# Leds_Switches.net
KiCad netlist of a schematic drawn in Altium Designer
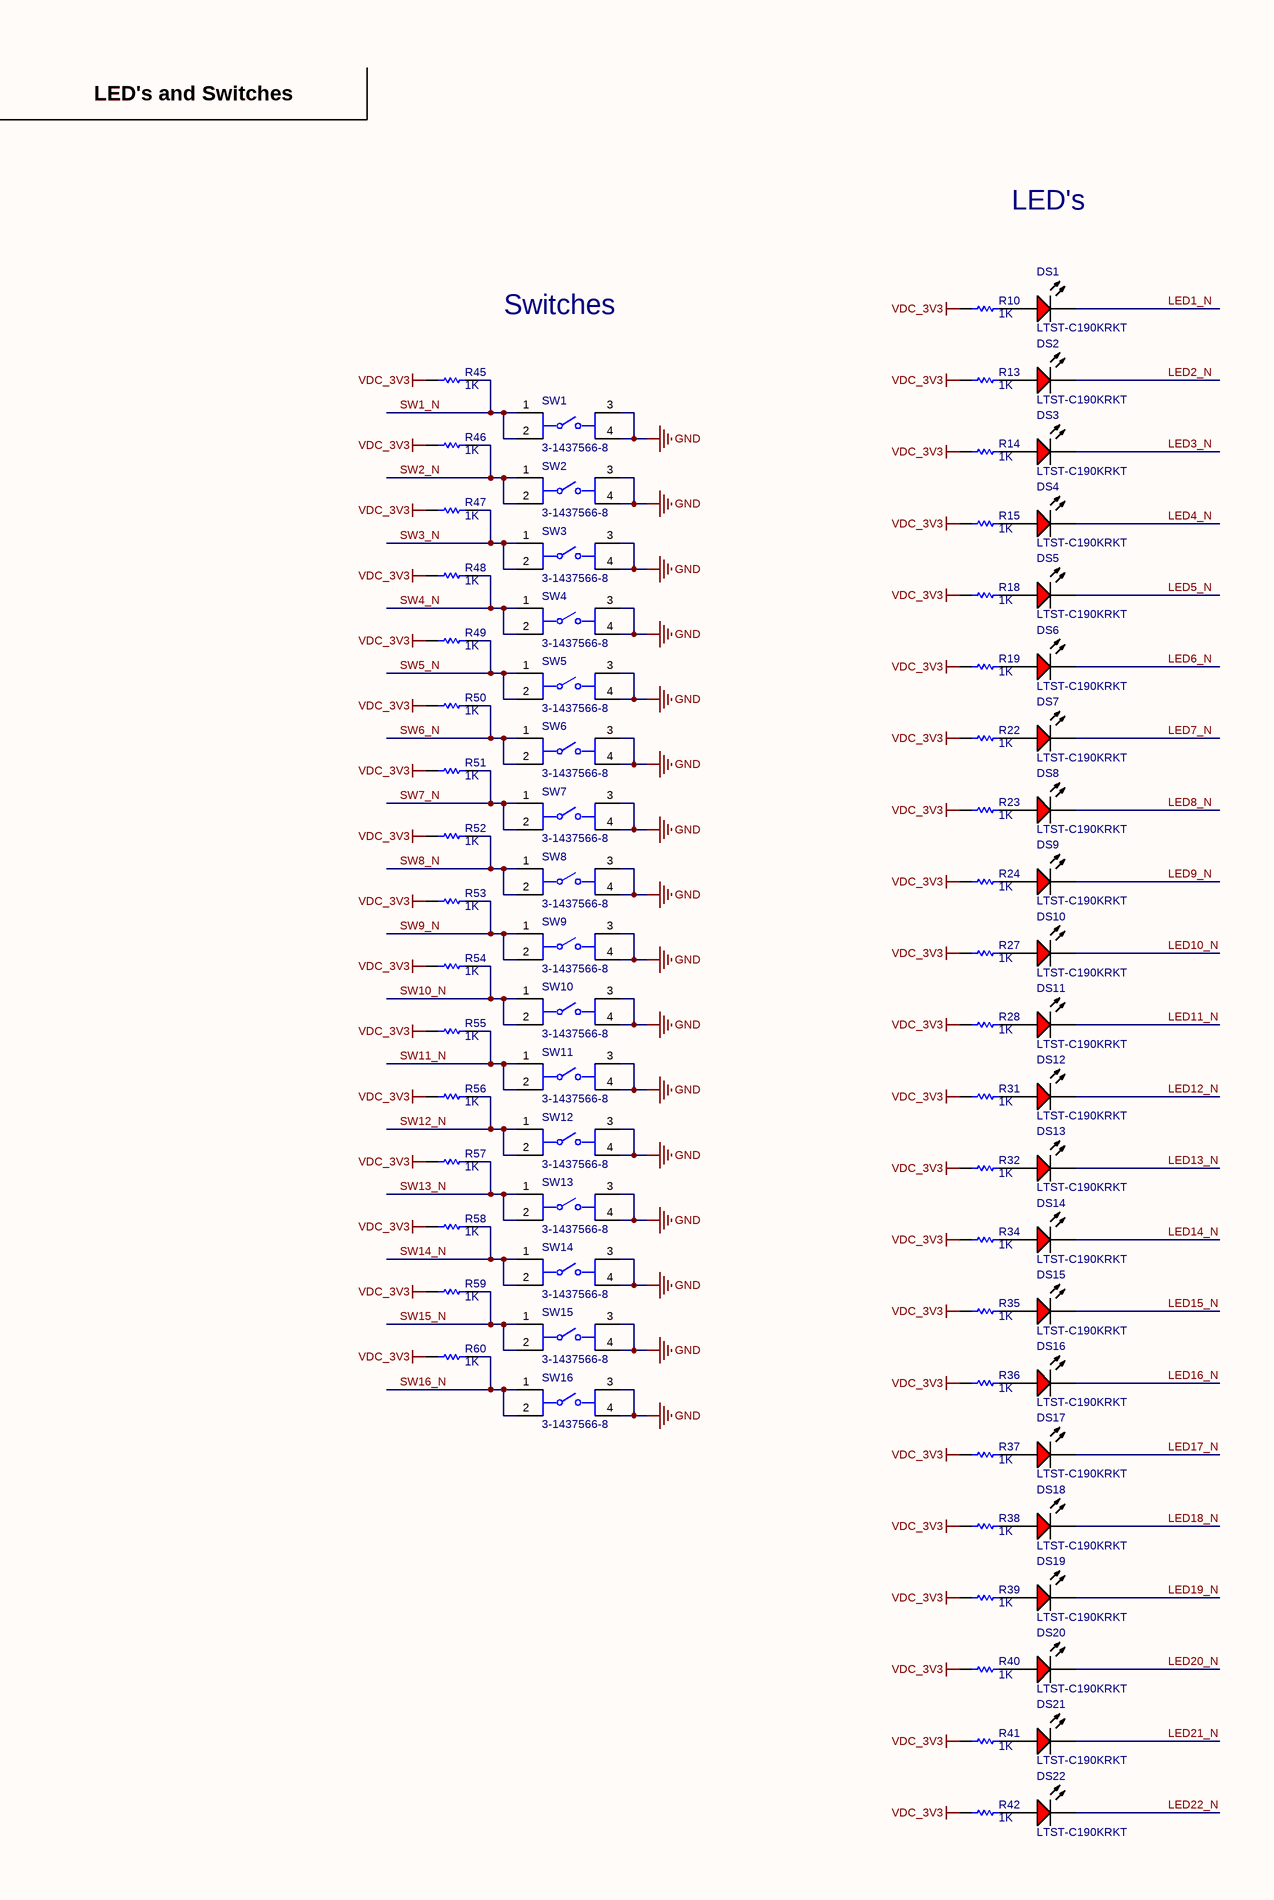
[diagram p0: Leds Switches.SchDoc, left]
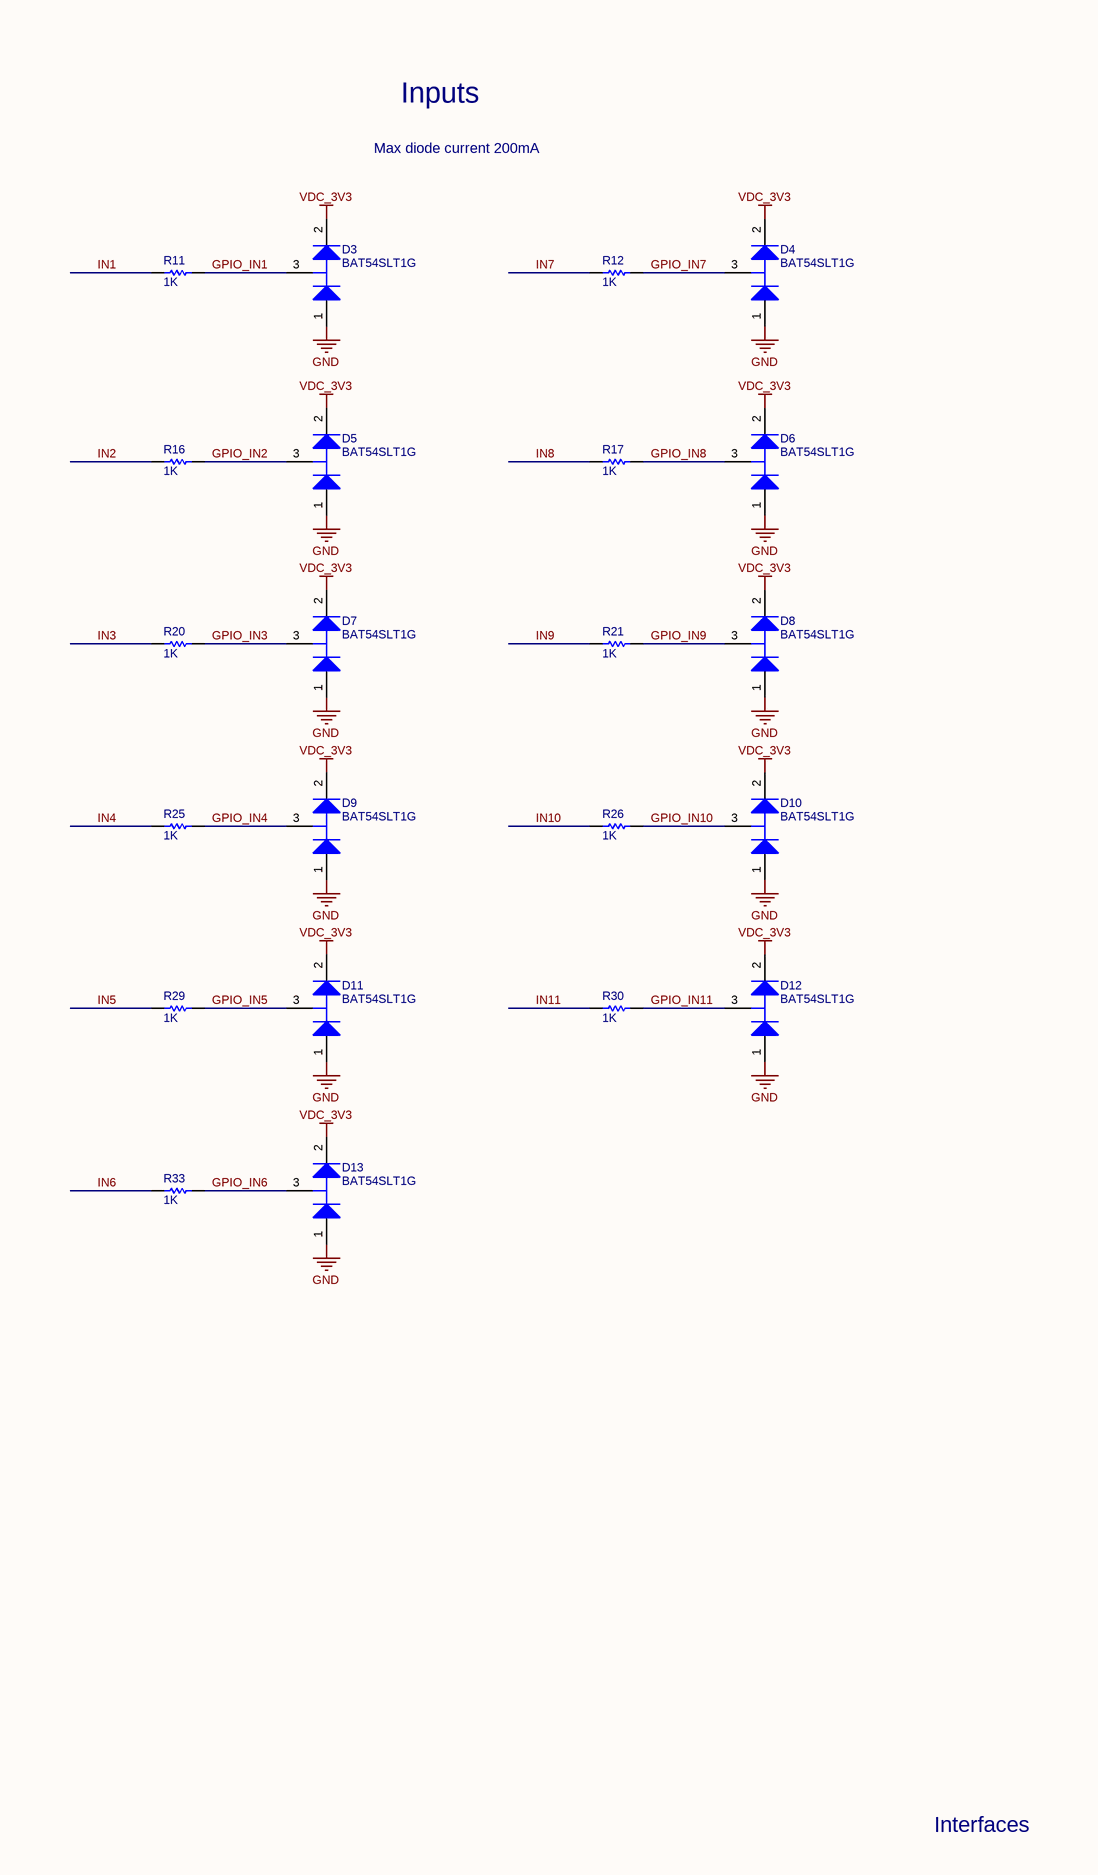
[diagram p1: Leds Switches.SchDoc, right]

(export (version "E")
  (design (tool "Eeschema 10.0.6"))
  (components
    (comp (ref "D3")
      (value "BAT54SLT1G")
      (footprint "ONSC-SOT-23-3-318-08_V")
      (description "Dual Series Schottky Barrier Diodes, 3-Pin SOT-23, Pb-Free, Tape and Reel")
      (fields (field (name "MANUFACTURER") "On Semiconductor"))
      (libsource (lib "Altium Content Vault") (part "ONSC-D-A1K2C3-3"))
    )
    (comp (ref "D4")
      (value "BAT54SLT1G")
      (footprint "ONSC-SOT-23-3-318-08_V")
      (description "Dual Series Schottky Barrier Diodes, 3-Pin SOT-23, Pb-Free, Tape and Reel")
      (fields (field (name "MANUFACTURER") "On Semiconductor"))
      (libsource (lib "Altium Content Vault") (part "ONSC-D-A1K2C3-3"))
    )
    (comp (ref "D5")
      (value "BAT54SLT1G")
      (footprint "ONSC-SOT-23-3-318-08_V")
      (description "Dual Series Schottky Barrier Diodes, 3-Pin SOT-23, Pb-Free, Tape and Reel")
      (fields (field (name "MANUFACTURER") "On Semiconductor"))
      (libsource (lib "Altium Content Vault") (part "ONSC-D-A1K2C3-3"))
    )
    (comp (ref "D6")
      (value "BAT54SLT1G")
      (footprint "ONSC-SOT-23-3-318-08_V")
      (description "Dual Series Schottky Barrier Diodes, 3-Pin SOT-23, Pb-Free, Tape and Reel")
      (fields (field (name "MANUFACTURER") "On Semiconductor"))
      (libsource (lib "Altium Content Vault") (part "ONSC-D-A1K2C3-3"))
    )
    (comp (ref "D7")
      (value "BAT54SLT1G")
      (footprint "ONSC-SOT-23-3-318-08_V")
      (description "Dual Series Schottky Barrier Diodes, 3-Pin SOT-23, Pb-Free, Tape and Reel")
      (fields (field (name "MANUFACTURER") "On Semiconductor"))
      (libsource (lib "Altium Content Vault") (part "ONSC-D-A1K2C3-3"))
    )
    (comp (ref "D8")
      (value "BAT54SLT1G")
      (footprint "ONSC-SOT-23-3-318-08_V")
      (description "Dual Series Schottky Barrier Diodes, 3-Pin SOT-23, Pb-Free, Tape and Reel")
      (fields (field (name "MANUFACTURER") "On Semiconductor"))
      (libsource (lib "Altium Content Vault") (part "ONSC-D-A1K2C3-3"))
    )
    (comp (ref "D9")
      (value "BAT54SLT1G")
      (footprint "ONSC-SOT-23-3-318-08_V")
      (description "Dual Series Schottky Barrier Diodes, 3-Pin SOT-23, Pb-Free, Tape and Reel")
      (fields (field (name "MANUFACTURER") "On Semiconductor"))
      (libsource (lib "Altium Content Vault") (part "ONSC-D-A1K2C3-3"))
    )
    (comp (ref "D10")
      (value "BAT54SLT1G")
      (footprint "ONSC-SOT-23-3-318-08_V")
      (description "Dual Series Schottky Barrier Diodes, 3-Pin SOT-23, Pb-Free, Tape and Reel")
      (fields (field (name "MANUFACTURER") "On Semiconductor"))
      (libsource (lib "Altium Content Vault") (part "ONSC-D-A1K2C3-3"))
    )
    (comp (ref "D11")
      (value "BAT54SLT1G")
      (footprint "ONSC-SOT-23-3-318-08_V")
      (description "Dual Series Schottky Barrier Diodes, 3-Pin SOT-23, Pb-Free, Tape and Reel")
      (fields (field (name "MANUFACTURER") "On Semiconductor"))
      (libsource (lib "Altium Content Vault") (part "ONSC-D-A1K2C3-3"))
    )
    (comp (ref "D12")
      (value "BAT54SLT1G")
      (footprint "ONSC-SOT-23-3-318-08_V")
      (description "Dual Series Schottky Barrier Diodes, 3-Pin SOT-23, Pb-Free, Tape and Reel")
      (fields (field (name "MANUFACTURER") "On Semiconductor"))
      (libsource (lib "Altium Content Vault") (part "ONSC-D-A1K2C3-3"))
    )
    (comp (ref "D13")
      (value "BAT54SLT1G")
      (footprint "ONSC-SOT-23-3-318-08_V")
      (description "Dual Series Schottky Barrier Diodes, 3-Pin SOT-23, Pb-Free, Tape and Reel")
      (fields (field (name "MANUFACTURER") "On Semiconductor"))
      (libsource (lib "Altium Content Vault") (part "ONSC-D-A1K2C3-3"))
    )
    (comp (ref "DS1")
      (value "LTST-C190KRKT")
      (footprint "LTST-C191KRKT_V")
      (description "LED Uni-Color Red, 62.5 mW, 5 V, -30 to 85 degC, 2-Pin SMD, RoHS, Tape and Reel")
      (fields (field (name "TOLERANCE") "20%"))
      (libsource (lib "Altium Content Vault") (part "LED-RED-AK-2"))
    )
    (comp (ref "DS2")
      (value "LTST-C190KRKT")
      (footprint "LTST-C191KRKT_V")
      (description "LED Uni-Color Red, 62.5 mW, 5 V, -30 to 85 degC, 2-Pin SMD, RoHS, Tape and Reel")
      (fields (field (name "TOLERANCE") "20%"))
      (libsource (lib "Altium Content Vault") (part "LED-RED-AK-2"))
    )
    (comp (ref "DS3")
      (value "LTST-C190KRKT")
      (footprint "LTST-C191KRKT_V")
      (description "LED Uni-Color Red, 62.5 mW, 5 V, -30 to 85 degC, 2-Pin SMD, RoHS, Tape and Reel")
      (fields (field (name "TOLERANCE") "20%"))
      (libsource (lib "Altium Content Vault") (part "LED-RED-AK-2"))
    )
    (comp (ref "DS4")
      (value "LTST-C190KRKT")
      (footprint "LTST-C191KRKT_V")
      (description "LED Uni-Color Red, 62.5 mW, 5 V, -30 to 85 degC, 2-Pin SMD, RoHS, Tape and Reel")
      (fields (field (name "TOLERANCE") "20%"))
      (libsource (lib "Altium Content Vault") (part "LED-RED-AK-2"))
    )
    (comp (ref "DS5")
      (value "LTST-C190KRKT")
      (footprint "LTST-C191KRKT_V")
      (description "LED Uni-Color Red, 62.5 mW, 5 V, -30 to 85 degC, 2-Pin SMD, RoHS, Tape and Reel")
      (fields (field (name "TOLERANCE") "20%"))
      (libsource (lib "Altium Content Vault") (part "LED-RED-AK-2"))
    )
    (comp (ref "DS6")
      (value "LTST-C190KRKT")
      (footprint "LTST-C191KRKT_V")
      (description "LED Uni-Color Red, 62.5 mW, 5 V, -30 to 85 degC, 2-Pin SMD, RoHS, Tape and Reel")
      (fields (field (name "TOLERANCE") "20%"))
      (libsource (lib "Altium Content Vault") (part "LED-RED-AK-2"))
    )
    (comp (ref "DS7")
      (value "LTST-C190KRKT")
      (footprint "LTST-C191KRKT_V")
      (description "LED Uni-Color Red, 62.5 mW, 5 V, -30 to 85 degC, 2-Pin SMD, RoHS, Tape and Reel")
      (fields (field (name "TOLERANCE") "20%"))
      (libsource (lib "Altium Content Vault") (part "LED-RED-AK-2"))
    )
    (comp (ref "DS8")
      (value "LTST-C190KRKT")
      (footprint "LTST-C191KRKT_V")
      (description "LED Uni-Color Red, 62.5 mW, 5 V, -30 to 85 degC, 2-Pin SMD, RoHS, Tape and Reel")
      (fields (field (name "TOLERANCE") "20%"))
      (libsource (lib "Altium Content Vault") (part "LED-RED-AK-2"))
    )
    (comp (ref "DS9")
      (value "LTST-C190KRKT")
      (footprint "LTST-C191KRKT_V")
      (description "LED Uni-Color Red, 62.5 mW, 5 V, -30 to 85 degC, 2-Pin SMD, RoHS, Tape and Reel")
      (fields (field (name "TOLERANCE") "20%"))
      (libsource (lib "Altium Content Vault") (part "LED-RED-AK-2"))
    )
    (comp (ref "DS10")
      (value "LTST-C190KRKT")
      (footprint "LTST-C191KRKT_V")
      (description "LED Uni-Color Red, 62.5 mW, 5 V, -30 to 85 degC, 2-Pin SMD, RoHS, Tape and Reel")
      (fields (field (name "TOLERANCE") "20%"))
      (libsource (lib "Altium Content Vault") (part "LED-RED-AK-2"))
    )
    (comp (ref "DS11")
      (value "LTST-C190KRKT")
      (footprint "LTST-C191KRKT_V")
      (description "LED Uni-Color Red, 62.5 mW, 5 V, -30 to 85 degC, 2-Pin SMD, RoHS, Tape and Reel")
      (fields (field (name "TOLERANCE") "20%"))
      (libsource (lib "Altium Content Vault") (part "LED-RED-AK-2"))
    )
    (comp (ref "DS12")
      (value "LTST-C190KRKT")
      (footprint "LTST-C191KRKT_V")
      (description "LED Uni-Color Red, 62.5 mW, 5 V, -30 to 85 degC, 2-Pin SMD, RoHS, Tape and Reel")
      (fields (field (name "TOLERANCE") "20%"))
      (libsource (lib "Altium Content Vault") (part "LED-RED-AK-2"))
    )
    (comp (ref "DS13")
      (value "LTST-C190KRKT")
      (footprint "LTST-C191KRKT_V")
      (description "LED Uni-Color Red, 62.5 mW, 5 V, -30 to 85 degC, 2-Pin SMD, RoHS, Tape and Reel")
      (fields (field (name "TOLERANCE") "20%"))
      (libsource (lib "Altium Content Vault") (part "LED-RED-AK-2"))
    )
    (comp (ref "DS14")
      (value "LTST-C190KRKT")
      (footprint "LTST-C191KRKT_V")
      (description "LED Uni-Color Red, 62.5 mW, 5 V, -30 to 85 degC, 2-Pin SMD, RoHS, Tape and Reel")
      (fields (field (name "TOLERANCE") "20%"))
      (libsource (lib "Altium Content Vault") (part "LED-RED-AK-2"))
    )
    (comp (ref "DS15")
      (value "LTST-C190KRKT")
      (footprint "LTST-C191KRKT_V")
      (description "LED Uni-Color Red, 62.5 mW, 5 V, -30 to 85 degC, 2-Pin SMD, RoHS, Tape and Reel")
      (fields (field (name "TOLERANCE") "20%"))
      (libsource (lib "Altium Content Vault") (part "LED-RED-AK-2"))
    )
    (comp (ref "DS16")
      (value "LTST-C190KRKT")
      (footprint "LTST-C191KRKT_V")
      (description "LED Uni-Color Red, 62.5 mW, 5 V, -30 to 85 degC, 2-Pin SMD, RoHS, Tape and Reel")
      (fields (field (name "TOLERANCE") "20%"))
      (libsource (lib "Altium Content Vault") (part "LED-RED-AK-2"))
    )
    (comp (ref "DS17")
      (value "LTST-C190KRKT")
      (footprint "LTST-C191KRKT_V")
      (description "LED Uni-Color Red, 62.5 mW, 5 V, -30 to 85 degC, 2-Pin SMD, RoHS, Tape and Reel")
      (fields (field (name "TOLERANCE") "20%"))
      (libsource (lib "Altium Content Vault") (part "LED-RED-AK-2"))
    )
    (comp (ref "DS18")
      (value "LTST-C190KRKT")
      (footprint "LTST-C191KRKT_V")
      (description "LED Uni-Color Red, 62.5 mW, 5 V, -30 to 85 degC, 2-Pin SMD, RoHS, Tape and Reel")
      (fields (field (name "TOLERANCE") "20%"))
      (libsource (lib "Altium Content Vault") (part "LED-RED-AK-2"))
    )
    (comp (ref "DS19")
      (value "LTST-C190KRKT")
      (footprint "LTST-C191KRKT_V")
      (description "LED Uni-Color Red, 62.5 mW, 5 V, -30 to 85 degC, 2-Pin SMD, RoHS, Tape and Reel")
      (fields (field (name "TOLERANCE") "20%"))
      (libsource (lib "Altium Content Vault") (part "LED-RED-AK-2"))
    )
    (comp (ref "DS20")
      (value "LTST-C190KRKT")
      (footprint "LTST-C191KRKT_V")
      (description "LED Uni-Color Red, 62.5 mW, 5 V, -30 to 85 degC, 2-Pin SMD, RoHS, Tape and Reel")
      (fields (field (name "TOLERANCE") "20%"))
      (libsource (lib "Altium Content Vault") (part "LED-RED-AK-2"))
    )
    (comp (ref "DS21")
      (value "LTST-C190KRKT")
      (footprint "LTST-C191KRKT_V")
      (description "LED Uni-Color Red, 62.5 mW, 5 V, -30 to 85 degC, 2-Pin SMD, RoHS, Tape and Reel")
      (fields (field (name "TOLERANCE") "20%"))
      (libsource (lib "Altium Content Vault") (part "LED-RED-AK-2"))
    )
    (comp (ref "DS22")
      (value "LTST-C190KRKT")
      (footprint "LTST-C191KRKT_V")
      (description "LED Uni-Color Red, 62.5 mW, 5 V, -30 to 85 degC, 2-Pin SMD, RoHS, Tape and Reel")
      (fields (field (name "TOLERANCE") "20%"))
      (libsource (lib "Altium Content Vault") (part "LED-RED-AK-2"))
    )
    (comp (ref "R10")
      (value "1K")
      (footprint "RESC1608X55X30ML15T15")
      (fields (field (name "PART NUMBER") "ERJ-3GEYJ102V") (field (name "MANUFACTURER") "Panasonic"))
      (libsource (lib "Altium Content Vault") (part "RES"))
    )
    (comp (ref "R11")
      (value "1K")
      (footprint "RESC1608X55X30ML15T15")
      (fields (field (name "PART NUMBER") "ERJ-3GEYJ102V") (field (name "MANUFACTURER") "Panasonic"))
      (libsource (lib "Altium Content Vault") (part "RES"))
    )
    (comp (ref "R12")
      (value "1K")
      (footprint "RESC1608X55X30ML15T15")
      (fields (field (name "PART NUMBER") "ERJ-3GEYJ102V") (field (name "MANUFACTURER") "Panasonic"))
      (libsource (lib "Altium Content Vault") (part "RES"))
    )
    (comp (ref "R13")
      (value "1K")
      (footprint "RESC1608X55X30ML15T15")
      (fields (field (name "PART NUMBER") "ERJ-3GEYJ102V") (field (name "MANUFACTURER") "Panasonic"))
      (libsource (lib "Altium Content Vault") (part "RES"))
    )
    (comp (ref "R14")
      (value "1K")
      (footprint "RESC1608X55X30ML15T15")
      (fields (field (name "PART NUMBER") "ERJ-3GEYJ102V") (field (name "MANUFACTURER") "Panasonic"))
      (libsource (lib "Altium Content Vault") (part "RES"))
    )
    (comp (ref "R15")
      (value "1K")
      (footprint "RESC1608X55X30ML15T15")
      (fields (field (name "PART NUMBER") "ERJ-3GEYJ102V") (field (name "MANUFACTURER") "Panasonic"))
      (libsource (lib "Altium Content Vault") (part "RES"))
    )
    (comp (ref "R16")
      (value "1K")
      (footprint "RESC1608X55X30ML15T15")
      (fields (field (name "PART NUMBER") "ERJ-3GEYJ102V") (field (name "MANUFACTURER") "Panasonic"))
      (libsource (lib "Altium Content Vault") (part "RES"))
    )
    (comp (ref "R17")
      (value "1K")
      (footprint "RESC1608X55X30ML15T15")
      (fields (field (name "PART NUMBER") "ERJ-3GEYJ102V") (field (name "MANUFACTURER") "Panasonic"))
      (libsource (lib "Altium Content Vault") (part "RES"))
    )
    (comp (ref "R18")
      (value "1K")
      (footprint "RESC1608X55X30ML15T15")
      (fields (field (name "PART NUMBER") "ERJ-3GEYJ102V") (field (name "MANUFACTURER") "Panasonic"))
      (libsource (lib "Altium Content Vault") (part "RES"))
    )
    (comp (ref "R19")
      (value "1K")
      (footprint "RESC1608X55X30ML15T15")
      (fields (field (name "PART NUMBER") "ERJ-3GEYJ102V") (field (name "MANUFACTURER") "Panasonic"))
      (libsource (lib "Altium Content Vault") (part "RES"))
    )
    (comp (ref "R20")
      (value "1K")
      (footprint "RESC1608X55X30ML15T15")
      (fields (field (name "PART NUMBER") "ERJ-3GEYJ102V") (field (name "MANUFACTURER") "Panasonic"))
      (libsource (lib "Altium Content Vault") (part "RES"))
    )
    (comp (ref "R21")
      (value "1K")
      (footprint "RESC1608X55X30ML15T15")
      (fields (field (name "PART NUMBER") "ERJ-3GEYJ102V") (field (name "MANUFACTURER") "Panasonic"))
      (libsource (lib "Altium Content Vault") (part "RES"))
    )
    (comp (ref "R22")
      (value "1K")
      (footprint "RESC1608X55X30ML15T15")
      (fields (field (name "PART NUMBER") "ERJ-3GEYJ102V") (field (name "MANUFACTURER") "Panasonic"))
      (libsource (lib "Altium Content Vault") (part "RES"))
    )
    (comp (ref "R23")
      (value "1K")
      (footprint "RESC1608X55X30ML15T15")
      (fields (field (name "PART NUMBER") "ERJ-3GEYJ102V") (field (name "MANUFACTURER") "Panasonic"))
      (libsource (lib "Altium Content Vault") (part "RES"))
    )
    (comp (ref "R24")
      (value "1K")
      (footprint "RESC1608X55X30ML15T15")
      (fields (field (name "PART NUMBER") "ERJ-3GEYJ102V") (field (name "MANUFACTURER") "Panasonic"))
      (libsource (lib "Altium Content Vault") (part "RES"))
    )
    (comp (ref "R25")
      (value "1K")
      (footprint "RESC1608X55X30ML15T15")
      (fields (field (name "PART NUMBER") "ERJ-3GEYJ102V") (field (name "MANUFACTURER") "Panasonic"))
      (libsource (lib "Altium Content Vault") (part "RES"))
    )
    (comp (ref "R26")
      (value "1K")
      (footprint "RESC1608X55X30ML15T15")
      (fields (field (name "PART NUMBER") "ERJ-3GEYJ102V") (field (name "MANUFACTURER") "Panasonic"))
      (libsource (lib "Altium Content Vault") (part "RES"))
    )
    (comp (ref "R27")
      (value "1K")
      (footprint "RESC1608X55X30ML15T15")
      (fields (field (name "PART NUMBER") "ERJ-3GEYJ102V") (field (name "MANUFACTURER") "Panasonic"))
      (libsource (lib "Altium Content Vault") (part "RES"))
    )
    (comp (ref "R28")
      (value "1K")
      (footprint "RESC1608X55X30ML15T15")
      (fields (field (name "PART NUMBER") "ERJ-3GEYJ102V") (field (name "MANUFACTURER") "Panasonic"))
      (libsource (lib "Altium Content Vault") (part "RES"))
    )
    (comp (ref "R29")
      (value "1K")
      (footprint "RESC1608X55X30ML15T15")
      (fields (field (name "PART NUMBER") "ERJ-3GEYJ102V") (field (name "MANUFACTURER") "Panasonic"))
      (libsource (lib "Altium Content Vault") (part "RES"))
    )
    (comp (ref "R30")
      (value "1K")
      (footprint "RESC1608X55X30ML15T15")
      (fields (field (name "PART NUMBER") "ERJ-3GEYJ102V") (field (name "MANUFACTURER") "Panasonic"))
      (libsource (lib "Altium Content Vault") (part "RES"))
    )
    (comp (ref "R31")
      (value "1K")
      (footprint "RESC1608X55X30ML15T15")
      (fields (field (name "PART NUMBER") "ERJ-3GEYJ102V") (field (name "MANUFACTURER") "Panasonic"))
      (libsource (lib "Altium Content Vault") (part "RES"))
    )
    (comp (ref "R32")
      (value "1K")
      (footprint "RESC1608X55X30ML15T15")
      (fields (field (name "PART NUMBER") "ERJ-3GEYJ102V") (field (name "MANUFACTURER") "Panasonic"))
      (libsource (lib "Altium Content Vault") (part "RES"))
    )
    (comp (ref "R33")
      (value "1K")
      (footprint "RESC1608X55X30ML15T15")
      (fields (field (name "PART NUMBER") "ERJ-3GEYJ102V") (field (name "MANUFACTURER") "Panasonic"))
      (libsource (lib "Altium Content Vault") (part "RES"))
    )
    (comp (ref "R34")
      (value "1K")
      (footprint "RESC1608X55X30ML15T15")
      (fields (field (name "PART NUMBER") "ERJ-3GEYJ102V") (field (name "MANUFACTURER") "Panasonic"))
      (libsource (lib "Altium Content Vault") (part "RES"))
    )
    (comp (ref "R35")
      (value "1K")
      (footprint "RESC1608X55X30ML15T15")
      (fields (field (name "PART NUMBER") "ERJ-3GEYJ102V") (field (name "MANUFACTURER") "Panasonic"))
      (libsource (lib "Altium Content Vault") (part "RES"))
    )
    (comp (ref "R36")
      (value "1K")
      (footprint "RESC1608X55X30ML15T15")
      (fields (field (name "PART NUMBER") "ERJ-3GEYJ102V") (field (name "MANUFACTURER") "Panasonic"))
      (libsource (lib "Altium Content Vault") (part "RES"))
    )
    (comp (ref "R37")
      (value "1K")
      (footprint "RESC1608X55X30ML15T15")
      (fields (field (name "PART NUMBER") "ERJ-3GEYJ102V") (field (name "MANUFACTURER") "Panasonic"))
      (libsource (lib "Altium Content Vault") (part "RES"))
    )
    (comp (ref "R38")
      (value "1K")
      (footprint "RESC1608X55X30ML15T15")
      (fields (field (name "PART NUMBER") "ERJ-3GEYJ102V") (field (name "MANUFACTURER") "Panasonic"))
      (libsource (lib "Altium Content Vault") (part "RES"))
    )
    (comp (ref "R39")
      (value "1K")
      (footprint "RESC1608X55X30ML15T15")
      (fields (field (name "PART NUMBER") "ERJ-3GEYJ102V") (field (name "MANUFACTURER") "Panasonic"))
      (libsource (lib "Altium Content Vault") (part "RES"))
    )
    (comp (ref "R40")
      (value "1K")
      (footprint "RESC1608X55X30ML15T15")
      (fields (field (name "PART NUMBER") "ERJ-3GEYJ102V") (field (name "MANUFACTURER") "Panasonic"))
      (libsource (lib "Altium Content Vault") (part "RES"))
    )
    (comp (ref "R41")
      (value "1K")
      (footprint "RESC1608X55X30ML15T15")
      (fields (field (name "PART NUMBER") "ERJ-3GEYJ102V") (field (name "MANUFACTURER") "Panasonic"))
      (libsource (lib "Altium Content Vault") (part "RES"))
    )
    (comp (ref "R42")
      (value "1K")
      (footprint "RESC1608X55X30ML15T15")
      (fields (field (name "PART NUMBER") "ERJ-3GEYJ102V") (field (name "MANUFACTURER") "Panasonic"))
      (libsource (lib "Altium Content Vault") (part "RES"))
    )
    (comp (ref "R45")
      (value "1K")
      (footprint "RESC1608X55X30ML15T15")
      (fields (field (name "PART NUMBER") "ERJ-3GEYJ102V") (field (name "MANUFACTURER") "Panasonic"))
      (libsource (lib "Altium Content Vault") (part "RES"))
    )
    (comp (ref "R46")
      (value "1K")
      (footprint "RESC1608X55X30ML15T15")
      (fields (field (name "PART NUMBER") "ERJ-3GEYJ102V") (field (name "MANUFACTURER") "Panasonic"))
      (libsource (lib "Altium Content Vault") (part "RES"))
    )
    (comp (ref "R47")
      (value "1K")
      (footprint "RESC1608X55X30ML15T15")
      (fields (field (name "PART NUMBER") "ERJ-3GEYJ102V") (field (name "MANUFACTURER") "Panasonic"))
      (libsource (lib "Altium Content Vault") (part "RES"))
    )
    (comp (ref "R48")
      (value "1K")
      (footprint "RESC1608X55X30ML15T15")
      (fields (field (name "PART NUMBER") "ERJ-3GEYJ102V") (field (name "MANUFACTURER") "Panasonic"))
      (libsource (lib "Altium Content Vault") (part "RES"))
    )
    (comp (ref "R49")
      (value "1K")
      (footprint "RESC1608X55X30ML15T15")
      (fields (field (name "PART NUMBER") "ERJ-3GEYJ102V") (field (name "MANUFACTURER") "Panasonic"))
      (libsource (lib "Altium Content Vault") (part "RES"))
    )
    (comp (ref "R50")
      (value "1K")
      (footprint "RESC1608X55X30ML15T15")
      (fields (field (name "PART NUMBER") "ERJ-3GEYJ102V") (field (name "MANUFACTURER") "Panasonic"))
      (libsource (lib "Altium Content Vault") (part "RES"))
    )
    (comp (ref "R51")
      (value "1K")
      (footprint "RESC1608X55X30ML15T15")
      (fields (field (name "PART NUMBER") "ERJ-3GEYJ102V") (field (name "MANUFACTURER") "Panasonic"))
      (libsource (lib "Altium Content Vault") (part "RES"))
    )
    (comp (ref "R52")
      (value "1K")
      (footprint "RESC1608X55X30ML15T15")
      (fields (field (name "PART NUMBER") "ERJ-3GEYJ102V") (field (name "MANUFACTURER") "Panasonic"))
      (libsource (lib "Altium Content Vault") (part "RES"))
    )
    (comp (ref "R53")
      (value "1K")
      (footprint "RESC1608X55X30ML15T15")
      (fields (field (name "PART NUMBER") "ERJ-3GEYJ102V") (field (name "MANUFACTURER") "Panasonic"))
      (libsource (lib "Altium Content Vault") (part "RES"))
    )
    (comp (ref "R54")
      (value "1K")
      (footprint "RESC1608X55X30ML15T15")
      (fields (field (name "PART NUMBER") "ERJ-3GEYJ102V") (field (name "MANUFACTURER") "Panasonic"))
      (libsource (lib "Altium Content Vault") (part "RES"))
    )
    (comp (ref "R55")
      (value "1K")
      (footprint "RESC1608X55X30ML15T15")
      (fields (field (name "PART NUMBER") "ERJ-3GEYJ102V") (field (name "MANUFACTURER") "Panasonic"))
      (libsource (lib "Altium Content Vault") (part "RES"))
    )
    (comp (ref "R56")
      (value "1K")
      (footprint "RESC1608X55X30ML15T15")
      (fields (field (name "PART NUMBER") "ERJ-3GEYJ102V") (field (name "MANUFACTURER") "Panasonic"))
      (libsource (lib "Altium Content Vault") (part "RES"))
    )
    (comp (ref "R57")
      (value "1K")
      (footprint "RESC1608X55X30ML15T15")
      (fields (field (name "PART NUMBER") "ERJ-3GEYJ102V") (field (name "MANUFACTURER") "Panasonic"))
      (libsource (lib "Altium Content Vault") (part "RES"))
    )
    (comp (ref "R58")
      (value "1K")
      (footprint "RESC1608X55X30ML15T15")
      (fields (field (name "PART NUMBER") "ERJ-3GEYJ102V") (field (name "MANUFACTURER") "Panasonic"))
      (libsource (lib "Altium Content Vault") (part "RES"))
    )
    (comp (ref "R59")
      (value "1K")
      (footprint "RESC1608X55X30ML15T15")
      (fields (field (name "PART NUMBER") "ERJ-3GEYJ102V") (field (name "MANUFACTURER") "Panasonic"))
      (libsource (lib "Altium Content Vault") (part "RES"))
    )
    (comp (ref "R60")
      (value "1K")
      (footprint "RESC1608X55X30ML15T15")
      (fields (field (name "PART NUMBER") "ERJ-3GEYJ102V") (field (name "MANUFACTURER") "Panasonic"))
      (libsource (lib "Altium Content Vault") (part "RES"))
    )
    (comp (ref "SW1")
      (value "Switch_TE_3-1437566-8_eec")
      (footprint "TECO-FSM6JSMA_V")
      (description "SWITCH Tactile Switch SPST-NO Top Actuated Surface Mount")
      (fields
        (field (name "MANUFACTURER") "TE")
        (field (name "MOUSER PART NUMBER") "506-3-1437566-8")
        (field (name "PART NUMBER") "3-1437566-8")
      )
      (libsource (lib "Switch_TE_3-1437566-8_eec") (part "Switch_TE_3-1437566-8_eec"))
    )
    (comp (ref "SW2")
      (value "Switch_TE_3-1437566-8_eec")
      (footprint "TECO-FSM6JSMA_V")
      (description "SWITCH Tactile Switch SPST-NO Top Actuated Surface Mount")
      (fields
        (field (name "MANUFACTURER") "TE")
        (field (name "MOUSER PART NUMBER") "506-3-1437566-8")
        (field (name "PART NUMBER") "3-1437566-8")
      )
      (libsource (lib "Switch_TE_3-1437566-8_eec") (part "Switch_TE_3-1437566-8_eec"))
    )
    (comp (ref "SW3")
      (value "Switch_TE_3-1437566-8_eec")
      (footprint "TECO-FSM6JSMA_V")
      (description "SWITCH Tactile Switch SPST-NO Top Actuated Surface Mount")
      (fields
        (field (name "MANUFACTURER") "TE")
        (field (name "MOUSER PART NUMBER") "506-3-1437566-8")
        (field (name "PART NUMBER") "3-1437566-8")
      )
      (libsource (lib "Switch_TE_3-1437566-8_eec") (part "Switch_TE_3-1437566-8_eec"))
    )
    (comp (ref "SW4")
      (value "Switch_TE_3-1437566-8_eec")
      (footprint "TECO-FSM6JSMA_V")
      (description "SWITCH Tactile Switch SPST-NO Top Actuated Surface Mount")
      (fields
        (field (name "MANUFACTURER") "TE")
        (field (name "MOUSER PART NUMBER") "506-3-1437566-8")
        (field (name "PART NUMBER") "3-1437566-8")
      )
      (libsource (lib "Switch_TE_3-1437566-8_eec") (part "Switch_TE_3-1437566-8_eec"))
    )
    (comp (ref "SW5")
      (value "Switch_TE_3-1437566-8_eec")
      (footprint "TECO-FSM6JSMA_V")
      (description "SWITCH Tactile Switch SPST-NO Top Actuated Surface Mount")
      (fields
        (field (name "MANUFACTURER") "TE")
        (field (name "MOUSER PART NUMBER") "506-3-1437566-8")
        (field (name "PART NUMBER") "3-1437566-8")
      )
      (libsource (lib "Switch_TE_3-1437566-8_eec") (part "Switch_TE_3-1437566-8_eec"))
    )
    (comp (ref "SW6")
      (value "Switch_TE_3-1437566-8_eec")
      (footprint "TECO-FSM6JSMA_V")
      (description "SWITCH Tactile Switch SPST-NO Top Actuated Surface Mount")
      (fields
        (field (name "MANUFACTURER") "TE")
        (field (name "MOUSER PART NUMBER") "506-3-1437566-8")
        (field (name "PART NUMBER") "3-1437566-8")
      )
      (libsource (lib "Switch_TE_3-1437566-8_eec") (part "Switch_TE_3-1437566-8_eec"))
    )
    (comp (ref "SW7")
      (value "Switch_TE_3-1437566-8_eec")
      (footprint "TECO-FSM6JSMA_V")
      (description "SWITCH Tactile Switch SPST-NO Top Actuated Surface Mount")
      (fields
        (field (name "MANUFACTURER") "TE")
        (field (name "MOUSER PART NUMBER") "506-3-1437566-8")
        (field (name "PART NUMBER") "3-1437566-8")
      )
      (libsource (lib "Switch_TE_3-1437566-8_eec") (part "Switch_TE_3-1437566-8_eec"))
    )
    (comp (ref "SW8")
      (value "Switch_TE_3-1437566-8_eec")
      (footprint "TECO-FSM6JSMA_V")
      (description "SWITCH Tactile Switch SPST-NO Top Actuated Surface Mount")
      (fields
        (field (name "MANUFACTURER") "TE")
        (field (name "MOUSER PART NUMBER") "506-3-1437566-8")
        (field (name "PART NUMBER") "3-1437566-8")
      )
      (libsource (lib "Switch_TE_3-1437566-8_eec") (part "Switch_TE_3-1437566-8_eec"))
    )
    (comp (ref "SW9")
      (value "Switch_TE_3-1437566-8_eec")
      (footprint "TECO-FSM6JSMA_V")
      (description "SWITCH Tactile Switch SPST-NO Top Actuated Surface Mount")
      (fields
        (field (name "MANUFACTURER") "TE")
        (field (name "MOUSER PART NUMBER") "506-3-1437566-8")
        (field (name "PART NUMBER") "3-1437566-8")
      )
      (libsource (lib "Switch_TE_3-1437566-8_eec") (part "Switch_TE_3-1437566-8_eec"))
    )
    (comp (ref "SW10")
      (value "Switch_TE_3-1437566-8_eec")
      (footprint "TECO-FSM6JSMA_V")
      (description "SWITCH Tactile Switch SPST-NO Top Actuated Surface Mount")
      (fields
        (field (name "MANUFACTURER") "TE")
        (field (name "MOUSER PART NUMBER") "506-3-1437566-8")
        (field (name "PART NUMBER") "3-1437566-8")
      )
      (libsource (lib "Switch_TE_3-1437566-8_eec") (part "Switch_TE_3-1437566-8_eec"))
    )
    (comp (ref "SW11")
      (value "Switch_TE_3-1437566-8_eec")
      (footprint "TECO-FSM6JSMA_V")
      (description "SWITCH Tactile Switch SPST-NO Top Actuated Surface Mount")
      (fields
        (field (name "MANUFACTURER") "TE")
        (field (name "MOUSER PART NUMBER") "506-3-1437566-8")
        (field (name "PART NUMBER") "3-1437566-8")
      )
      (libsource (lib "Switch_TE_3-1437566-8_eec") (part "Switch_TE_3-1437566-8_eec"))
    )
    (comp (ref "SW12")
      (value "Switch_TE_3-1437566-8_eec")
      (footprint "TECO-FSM6JSMA_V")
      (description "SWITCH Tactile Switch SPST-NO Top Actuated Surface Mount")
      (fields
        (field (name "MANUFACTURER") "TE")
        (field (name "MOUSER PART NUMBER") "506-3-1437566-8")
        (field (name "PART NUMBER") "3-1437566-8")
      )
      (libsource (lib "Switch_TE_3-1437566-8_eec") (part "Switch_TE_3-1437566-8_eec"))
    )
    (comp (ref "SW13")
      (value "Switch_TE_3-1437566-8_eec")
      (footprint "TECO-FSM6JSMA_V")
      (description "SWITCH Tactile Switch SPST-NO Top Actuated Surface Mount")
      (fields
        (field (name "MANUFACTURER") "TE")
        (field (name "MOUSER PART NUMBER") "506-3-1437566-8")
        (field (name "PART NUMBER") "3-1437566-8")
      )
      (libsource (lib "Switch_TE_3-1437566-8_eec") (part "Switch_TE_3-1437566-8_eec"))
    )
    (comp (ref "SW14")
      (value "Switch_TE_3-1437566-8_eec")
      (footprint "TECO-FSM6JSMA_V")
      (description "SWITCH Tactile Switch SPST-NO Top Actuated Surface Mount")
      (fields
        (field (name "MANUFACTURER") "TE")
        (field (name "MOUSER PART NUMBER") "506-3-1437566-8")
        (field (name "PART NUMBER") "3-1437566-8")
      )
      (libsource (lib "Switch_TE_3-1437566-8_eec") (part "Switch_TE_3-1437566-8_eec"))
    )
    (comp (ref "SW15")
      (value "Switch_TE_3-1437566-8_eec")
      (footprint "TECO-FSM6JSMA_V")
      (description "SWITCH Tactile Switch SPST-NO Top Actuated Surface Mount")
      (fields
        (field (name "MANUFACTURER") "TE")
        (field (name "MOUSER PART NUMBER") "506-3-1437566-8")
        (field (name "PART NUMBER") "3-1437566-8")
      )
      (libsource (lib "Switch_TE_3-1437566-8_eec") (part "Switch_TE_3-1437566-8_eec"))
    )
    (comp (ref "SW16")
      (value "Switch_TE_3-1437566-8_eec")
      (footprint "TECO-FSM6JSMA_V")
      (description "SWITCH Tactile Switch SPST-NO Top Actuated Surface Mount")
      (fields
        (field (name "MANUFACTURER") "TE")
        (field (name "MOUSER PART NUMBER") "506-3-1437566-8")
        (field (name "PART NUMBER") "3-1437566-8")
      )
      (libsource (lib "Switch_TE_3-1437566-8_eec") (part "Switch_TE_3-1437566-8_eec"))
    )
  )
  (nets
    (net (code "1") (name "/GPIO_IN1") (class "Default")
      (node (ref "D3") (pin "3") (pinfunction "K/A_3") (pintype "passive"))
      (node (ref "R11") (pin "1") (pinfunction "1_1") (pintype "passive"))
    )
    (net (code "2") (name "/GPIO_IN2") (class "Default")
      (node (ref "D5") (pin "3") (pinfunction "K/A_3") (pintype "passive"))
      (node (ref "R16") (pin "1") (pinfunction "1_1") (pintype "passive"))
    )
    (net (code "3") (name "/GPIO_IN3") (class "Default")
      (node (ref "D7") (pin "3") (pinfunction "K/A_3") (pintype "passive"))
      (node (ref "R20") (pin "1") (pinfunction "1_1") (pintype "passive"))
    )
    (net (code "4") (name "/GPIO_IN4") (class "Default")
      (node (ref "D9") (pin "3") (pinfunction "K/A_3") (pintype "passive"))
      (node (ref "R25") (pin "1") (pinfunction "1_1") (pintype "passive"))
    )
    (net (code "5") (name "/GPIO_IN5") (class "Default")
      (node (ref "D11") (pin "3") (pinfunction "K/A_3") (pintype "passive"))
      (node (ref "R29") (pin "1") (pinfunction "1_1") (pintype "passive"))
    )
    (net (code "6") (name "/GPIO_IN6") (class "Default")
      (node (ref "D13") (pin "3") (pinfunction "K/A_3") (pintype "passive"))
      (node (ref "R33") (pin "1") (pinfunction "1_1") (pintype "passive"))
    )
    (net (code "7") (name "/GPIO_IN7") (class "Default")
      (node (ref "D4") (pin "3") (pinfunction "K/A_3") (pintype "passive"))
      (node (ref "R12") (pin "1") (pinfunction "1_1") (pintype "passive"))
    )
    (net (code "8") (name "/GPIO_IN8") (class "Default")
      (node (ref "D6") (pin "3") (pinfunction "K/A_3") (pintype "passive"))
      (node (ref "R17") (pin "1") (pinfunction "1_1") (pintype "passive"))
    )
    (net (code "9") (name "/GPIO_IN9") (class "Default")
      (node (ref "D8") (pin "3") (pinfunction "K/A_3") (pintype "passive"))
      (node (ref "R21") (pin "1") (pinfunction "1_1") (pintype "passive"))
    )
    (net (code "10") (name "/GPIO_IN10") (class "Default")
      (node (ref "D10") (pin "3") (pinfunction "K/A_3") (pintype "passive"))
      (node (ref "R26") (pin "1") (pinfunction "1_1") (pintype "passive"))
    )
    (net (code "11") (name "/GPIO_IN11") (class "Default")
      (node (ref "D12") (pin "3") (pinfunction "K/A_3") (pintype "passive"))
      (node (ref "R30") (pin "1") (pinfunction "1_1") (pintype "passive"))
    )
    (net (code "12") (name "/IN1") (class "Default")
      (node (ref "R11") (pin "2") (pinfunction "2_2") (pintype "passive"))
    )
    (net (code "13") (name "/IN2") (class "Default")
      (node (ref "R16") (pin "2") (pinfunction "2_2") (pintype "passive"))
    )
    (net (code "14") (name "/IN3") (class "Default")
      (node (ref "R20") (pin "2") (pinfunction "2_2") (pintype "passive"))
    )
    (net (code "15") (name "/IN4") (class "Default")
      (node (ref "R25") (pin "2") (pinfunction "2_2") (pintype "passive"))
    )
    (net (code "16") (name "/IN5") (class "Default")
      (node (ref "R29") (pin "2") (pinfunction "2_2") (pintype "passive"))
    )
    (net (code "17") (name "/IN6") (class "Default")
      (node (ref "R33") (pin "2") (pinfunction "2_2") (pintype "passive"))
    )
    (net (code "18") (name "/IN7") (class "Default")
      (node (ref "R12") (pin "2") (pinfunction "2_2") (pintype "passive"))
    )
    (net (code "19") (name "/IN8") (class "Default")
      (node (ref "R17") (pin "2") (pinfunction "2_2") (pintype "passive"))
    )
    (net (code "20") (name "/IN9") (class "Default")
      (node (ref "R21") (pin "2") (pinfunction "2_2") (pintype "passive"))
    )
    (net (code "21") (name "/IN10") (class "Default")
      (node (ref "R26") (pin "2") (pinfunction "2_2") (pintype "passive"))
    )
    (net (code "22") (name "/IN11") (class "Default")
      (node (ref "R30") (pin "2") (pinfunction "2_2") (pintype "passive"))
    )
    (net (code "23") (name "/LED1_N") (class "Default")
      (node (ref "DS1") (pin "2") (pinfunction "K_2") (pintype "passive"))
    )
    (net (code "24") (name "/LED2_N") (class "Default")
      (node (ref "DS2") (pin "2") (pinfunction "K_2") (pintype "passive"))
    )
    (net (code "25") (name "/LED3_N") (class "Default")
      (node (ref "DS3") (pin "2") (pinfunction "K_2") (pintype "passive"))
    )
    (net (code "26") (name "/LED4_N") (class "Default")
      (node (ref "DS4") (pin "2") (pinfunction "K_2") (pintype "passive"))
    )
    (net (code "27") (name "/LED5_N") (class "Default")
      (node (ref "DS5") (pin "2") (pinfunction "K_2") (pintype "passive"))
    )
    (net (code "28") (name "/LED6_N") (class "Default")
      (node (ref "DS6") (pin "2") (pinfunction "K_2") (pintype "passive"))
    )
    (net (code "29") (name "/LED7_N") (class "Default")
      (node (ref "DS7") (pin "2") (pinfunction "K_2") (pintype "passive"))
    )
    (net (code "30") (name "/LED8_N") (class "Default")
      (node (ref "DS8") (pin "2") (pinfunction "K_2") (pintype "passive"))
    )
    (net (code "31") (name "/LED9_N") (class "Default")
      (node (ref "DS9") (pin "2") (pinfunction "K_2") (pintype "passive"))
    )
    (net (code "32") (name "/LED10_N") (class "Default")
      (node (ref "DS10") (pin "2") (pinfunction "K_2") (pintype "passive"))
    )
    (net (code "33") (name "/LED11_N") (class "Default")
      (node (ref "DS11") (pin "2") (pinfunction "K_2") (pintype "passive"))
    )
    (net (code "34") (name "/LED12_N") (class "Default")
      (node (ref "DS12") (pin "2") (pinfunction "K_2") (pintype "passive"))
    )
    (net (code "35") (name "/LED13_N") (class "Default")
      (node (ref "DS13") (pin "2") (pinfunction "K_2") (pintype "passive"))
    )
    (net (code "36") (name "/LED14_N") (class "Default")
      (node (ref "DS14") (pin "2") (pinfunction "K_2") (pintype "passive"))
    )
    (net (code "37") (name "/LED15_N") (class "Default")
      (node (ref "DS15") (pin "2") (pinfunction "K_2") (pintype "passive"))
    )
    (net (code "38") (name "/LED16_N") (class "Default")
      (node (ref "DS16") (pin "2") (pinfunction "K_2") (pintype "passive"))
    )
    (net (code "39") (name "/LED17_N") (class "Default")
      (node (ref "DS17") (pin "2") (pinfunction "K_2") (pintype "passive"))
    )
    (net (code "40") (name "/LED18_N") (class "Default")
      (node (ref "DS18") (pin "2") (pinfunction "K_2") (pintype "passive"))
    )
    (net (code "41") (name "/LED19_N") (class "Default")
      (node (ref "DS19") (pin "2") (pinfunction "K_2") (pintype "passive"))
    )
    (net (code "42") (name "/LED20_N") (class "Default")
      (node (ref "DS20") (pin "2") (pinfunction "K_2") (pintype "passive"))
    )
    (net (code "43") (name "/LED21_N") (class "Default")
      (node (ref "DS21") (pin "2") (pinfunction "K_2") (pintype "passive"))
    )
    (net (code "44") (name "/LED22_N") (class "Default")
      (node (ref "DS22") (pin "2") (pinfunction "K_2") (pintype "passive"))
    )
    (net (code "45") (name "/SW1_N") (class "Default")
      (node (ref "R45") (pin "2") (pinfunction "2_2") (pintype "passive"))
      (node (ref "SW1") (pin "1") (pinfunction "1_1") (pintype "passive"))
      (node (ref "SW1") (pin "2") (pinfunction "2_2") (pintype "passive"))
    )
    (net (code "46") (name "/SW2_N") (class "Default")
      (node (ref "R46") (pin "2") (pinfunction "2_2") (pintype "passive"))
      (node (ref "SW2") (pin "1") (pinfunction "1_1") (pintype "passive"))
      (node (ref "SW2") (pin "2") (pinfunction "2_2") (pintype "passive"))
    )
    (net (code "47") (name "/SW3_N") (class "Default")
      (node (ref "R47") (pin "2") (pinfunction "2_2") (pintype "passive"))
      (node (ref "SW3") (pin "1") (pinfunction "1_1") (pintype "passive"))
      (node (ref "SW3") (pin "2") (pinfunction "2_2") (pintype "passive"))
    )
    (net (code "48") (name "/SW4_N") (class "Default")
      (node (ref "R48") (pin "2") (pinfunction "2_2") (pintype "passive"))
      (node (ref "SW4") (pin "1") (pinfunction "1_1") (pintype "passive"))
      (node (ref "SW4") (pin "2") (pinfunction "2_2") (pintype "passive"))
    )
    (net (code "49") (name "/SW5_N") (class "Default")
      (node (ref "R49") (pin "2") (pinfunction "2_2") (pintype "passive"))
      (node (ref "SW5") (pin "1") (pinfunction "1_1") (pintype "passive"))
      (node (ref "SW5") (pin "2") (pinfunction "2_2") (pintype "passive"))
    )
    (net (code "50") (name "/SW6_N") (class "Default")
      (node (ref "R50") (pin "2") (pinfunction "2_2") (pintype "passive"))
      (node (ref "SW6") (pin "1") (pinfunction "1_1") (pintype "passive"))
      (node (ref "SW6") (pin "2") (pinfunction "2_2") (pintype "passive"))
    )
    (net (code "51") (name "/SW7_N") (class "Default")
      (node (ref "R51") (pin "2") (pinfunction "2_2") (pintype "passive"))
      (node (ref "SW7") (pin "1") (pinfunction "1_1") (pintype "passive"))
      (node (ref "SW7") (pin "2") (pinfunction "2_2") (pintype "passive"))
    )
    (net (code "52") (name "/SW8_N") (class "Default")
      (node (ref "R52") (pin "2") (pinfunction "2_2") (pintype "passive"))
      (node (ref "SW8") (pin "1") (pinfunction "1_1") (pintype "passive"))
      (node (ref "SW8") (pin "2") (pinfunction "2_2") (pintype "passive"))
    )
    (net (code "53") (name "/SW9_N") (class "Default")
      (node (ref "R53") (pin "2") (pinfunction "2_2") (pintype "passive"))
      (node (ref "SW9") (pin "1") (pinfunction "1_1") (pintype "passive"))
      (node (ref "SW9") (pin "2") (pinfunction "2_2") (pintype "passive"))
    )
    (net (code "54") (name "/SW10_N") (class "Default")
      (node (ref "R54") (pin "2") (pinfunction "2_2") (pintype "passive"))
      (node (ref "SW10") (pin "1") (pinfunction "1_1") (pintype "passive"))
      (node (ref "SW10") (pin "2") (pinfunction "2_2") (pintype "passive"))
    )
    (net (code "55") (name "/SW11_N") (class "Default")
      (node (ref "R55") (pin "2") (pinfunction "2_2") (pintype "passive"))
      (node (ref "SW11") (pin "1") (pinfunction "1_1") (pintype "passive"))
      (node (ref "SW11") (pin "2") (pinfunction "2_2") (pintype "passive"))
    )
    (net (code "56") (name "/SW12_N") (class "Default")
      (node (ref "R56") (pin "2") (pinfunction "2_2") (pintype "passive"))
      (node (ref "SW12") (pin "1") (pinfunction "1_1") (pintype "passive"))
      (node (ref "SW12") (pin "2") (pinfunction "2_2") (pintype "passive"))
    )
    (net (code "57") (name "/SW13_N") (class "Default")
      (node (ref "R57") (pin "2") (pinfunction "2_2") (pintype "passive"))
      (node (ref "SW13") (pin "1") (pinfunction "1_1") (pintype "passive"))
      (node (ref "SW13") (pin "2") (pinfunction "2_2") (pintype "passive"))
    )
    (net (code "58") (name "/SW14_N") (class "Default")
      (node (ref "R58") (pin "2") (pinfunction "2_2") (pintype "passive"))
      (node (ref "SW14") (pin "1") (pinfunction "1_1") (pintype "passive"))
      (node (ref "SW14") (pin "2") (pinfunction "2_2") (pintype "passive"))
    )
    (net (code "59") (name "/SW15_N") (class "Default")
      (node (ref "R59") (pin "2") (pinfunction "2_2") (pintype "passive"))
      (node (ref "SW15") (pin "1") (pinfunction "1_1") (pintype "passive"))
      (node (ref "SW15") (pin "2") (pinfunction "2_2") (pintype "passive"))
    )
    (net (code "60") (name "/SW16_N") (class "Default")
      (node (ref "R60") (pin "2") (pinfunction "2_2") (pintype "passive"))
      (node (ref "SW16") (pin "1") (pinfunction "1_1") (pintype "passive"))
      (node (ref "SW16") (pin "2") (pinfunction "2_2") (pintype "passive"))
    )
    (net (code "61") (name "GND") (class "Default")
      (node (ref "D10") (pin "1") (pinfunction "A_1") (pintype "passive"))
      (node (ref "D11") (pin "1") (pinfunction "A_1") (pintype "passive"))
      (node (ref "D12") (pin "1") (pinfunction "A_1") (pintype "passive"))
      (node (ref "D13") (pin "1") (pinfunction "A_1") (pintype "passive"))
      (node (ref "D3") (pin "1") (pinfunction "A_1") (pintype "passive"))
      (node (ref "D4") (pin "1") (pinfunction "A_1") (pintype "passive"))
      (node (ref "D5") (pin "1") (pinfunction "A_1") (pintype "passive"))
      (node (ref "D6") (pin "1") (pinfunction "A_1") (pintype "passive"))
      (node (ref "D7") (pin "1") (pinfunction "A_1") (pintype "passive"))
      (node (ref "D8") (pin "1") (pinfunction "A_1") (pintype "passive"))
      (node (ref "D9") (pin "1") (pinfunction "A_1") (pintype "passive"))
      (node (ref "SW1") (pin "3") (pinfunction "3_3") (pintype "passive"))
      (node (ref "SW1") (pin "4") (pinfunction "4_4") (pintype "passive"))
      (node (ref "SW10") (pin "3") (pinfunction "3_3") (pintype "passive"))
      (node (ref "SW10") (pin "4") (pinfunction "4_4") (pintype "passive"))
      (node (ref "SW11") (pin "3") (pinfunction "3_3") (pintype "passive"))
      (node (ref "SW11") (pin "4") (pinfunction "4_4") (pintype "passive"))
      (node (ref "SW12") (pin "3") (pinfunction "3_3") (pintype "passive"))
      (node (ref "SW12") (pin "4") (pinfunction "4_4") (pintype "passive"))
      (node (ref "SW13") (pin "3") (pinfunction "3_3") (pintype "passive"))
      (node (ref "SW13") (pin "4") (pinfunction "4_4") (pintype "passive"))
      (node (ref "SW14") (pin "3") (pinfunction "3_3") (pintype "passive"))
      (node (ref "SW14") (pin "4") (pinfunction "4_4") (pintype "passive"))
      (node (ref "SW15") (pin "3") (pinfunction "3_3") (pintype "passive"))
      (node (ref "SW15") (pin "4") (pinfunction "4_4") (pintype "passive"))
      (node (ref "SW16") (pin "3") (pinfunction "3_3") (pintype "passive"))
      (node (ref "SW16") (pin "4") (pinfunction "4_4") (pintype "passive"))
      (node (ref "SW2") (pin "3") (pinfunction "3_3") (pintype "passive"))
      (node (ref "SW2") (pin "4") (pinfunction "4_4") (pintype "passive"))
      (node (ref "SW3") (pin "3") (pinfunction "3_3") (pintype "passive"))
      (node (ref "SW3") (pin "4") (pinfunction "4_4") (pintype "passive"))
      (node (ref "SW4") (pin "3") (pinfunction "3_3") (pintype "passive"))
      (node (ref "SW4") (pin "4") (pinfunction "4_4") (pintype "passive"))
      (node (ref "SW5") (pin "3") (pinfunction "3_3") (pintype "passive"))
      (node (ref "SW5") (pin "4") (pinfunction "4_4") (pintype "passive"))
      (node (ref "SW6") (pin "3") (pinfunction "3_3") (pintype "passive"))
      (node (ref "SW6") (pin "4") (pinfunction "4_4") (pintype "passive"))
      (node (ref "SW7") (pin "3") (pinfunction "3_3") (pintype "passive"))
      (node (ref "SW7") (pin "4") (pinfunction "4_4") (pintype "passive"))
      (node (ref "SW8") (pin "3") (pinfunction "3_3") (pintype "passive"))
      (node (ref "SW8") (pin "4") (pinfunction "4_4") (pintype "passive"))
      (node (ref "SW9") (pin "3") (pinfunction "3_3") (pintype "passive"))
      (node (ref "SW9") (pin "4") (pinfunction "4_4") (pintype "passive"))
    )
    (net (code "62") (name "Net-(DS1-A)") (class "Default")
      (node (ref "DS1") (pin "1") (pinfunction "A_1") (pintype "passive"))
      (node (ref "R10") (pin "2") (pinfunction "2_2") (pintype "passive"))
    )
    (net (code "63") (name "Net-(DS2-A)") (class "Default")
      (node (ref "DS2") (pin "1") (pinfunction "A_1") (pintype "passive"))
      (node (ref "R13") (pin "2") (pinfunction "2_2") (pintype "passive"))
    )
    (net (code "64") (name "Net-(DS3-A)") (class "Default")
      (node (ref "DS3") (pin "1") (pinfunction "A_1") (pintype "passive"))
      (node (ref "R14") (pin "2") (pinfunction "2_2") (pintype "passive"))
    )
    (net (code "65") (name "Net-(DS4-A)") (class "Default")
      (node (ref "DS4") (pin "1") (pinfunction "A_1") (pintype "passive"))
      (node (ref "R15") (pin "2") (pinfunction "2_2") (pintype "passive"))
    )
    (net (code "66") (name "Net-(DS5-A)") (class "Default")
      (node (ref "DS5") (pin "1") (pinfunction "A_1") (pintype "passive"))
      (node (ref "R18") (pin "2") (pinfunction "2_2") (pintype "passive"))
    )
    (net (code "67") (name "Net-(DS6-A)") (class "Default")
      (node (ref "DS6") (pin "1") (pinfunction "A_1") (pintype "passive"))
      (node (ref "R19") (pin "2") (pinfunction "2_2") (pintype "passive"))
    )
    (net (code "68") (name "Net-(DS7-A)") (class "Default")
      (node (ref "DS7") (pin "1") (pinfunction "A_1") (pintype "passive"))
      (node (ref "R22") (pin "2") (pinfunction "2_2") (pintype "passive"))
    )
    (net (code "69") (name "Net-(DS8-A)") (class "Default")
      (node (ref "DS8") (pin "1") (pinfunction "A_1") (pintype "passive"))
      (node (ref "R23") (pin "2") (pinfunction "2_2") (pintype "passive"))
    )
    (net (code "70") (name "Net-(DS9-A)") (class "Default")
      (node (ref "DS9") (pin "1") (pinfunction "A_1") (pintype "passive"))
      (node (ref "R24") (pin "2") (pinfunction "2_2") (pintype "passive"))
    )
    (net (code "71") (name "Net-(DS10-A)") (class "Default")
      (node (ref "DS10") (pin "1") (pinfunction "A_1") (pintype "passive"))
      (node (ref "R27") (pin "2") (pinfunction "2_2") (pintype "passive"))
    )
    (net (code "72") (name "Net-(DS11-A)") (class "Default")
      (node (ref "DS11") (pin "1") (pinfunction "A_1") (pintype "passive"))
      (node (ref "R28") (pin "2") (pinfunction "2_2") (pintype "passive"))
    )
    (net (code "73") (name "Net-(DS12-A)") (class "Default")
      (node (ref "DS12") (pin "1") (pinfunction "A_1") (pintype "passive"))
      (node (ref "R31") (pin "2") (pinfunction "2_2") (pintype "passive"))
    )
    (net (code "74") (name "Net-(DS13-A)") (class "Default")
      (node (ref "DS13") (pin "1") (pinfunction "A_1") (pintype "passive"))
      (node (ref "R32") (pin "2") (pinfunction "2_2") (pintype "passive"))
    )
    (net (code "75") (name "Net-(DS14-A)") (class "Default")
      (node (ref "DS14") (pin "1") (pinfunction "A_1") (pintype "passive"))
      (node (ref "R34") (pin "2") (pinfunction "2_2") (pintype "passive"))
    )
    (net (code "76") (name "Net-(DS15-A)") (class "Default")
      (node (ref "DS15") (pin "1") (pinfunction "A_1") (pintype "passive"))
      (node (ref "R35") (pin "2") (pinfunction "2_2") (pintype "passive"))
    )
    (net (code "77") (name "Net-(DS16-A)") (class "Default")
      (node (ref "DS16") (pin "1") (pinfunction "A_1") (pintype "passive"))
      (node (ref "R36") (pin "2") (pinfunction "2_2") (pintype "passive"))
    )
    (net (code "78") (name "Net-(DS17-A)") (class "Default")
      (node (ref "DS17") (pin "1") (pinfunction "A_1") (pintype "passive"))
      (node (ref "R37") (pin "2") (pinfunction "2_2") (pintype "passive"))
    )
    (net (code "79") (name "Net-(DS18-A)") (class "Default")
      (node (ref "DS18") (pin "1") (pinfunction "A_1") (pintype "passive"))
      (node (ref "R38") (pin "2") (pinfunction "2_2") (pintype "passive"))
    )
    (net (code "80") (name "Net-(DS19-A)") (class "Default")
      (node (ref "DS19") (pin "1") (pinfunction "A_1") (pintype "passive"))
      (node (ref "R39") (pin "2") (pinfunction "2_2") (pintype "passive"))
    )
    (net (code "81") (name "Net-(DS20-A)") (class "Default")
      (node (ref "DS20") (pin "1") (pinfunction "A_1") (pintype "passive"))
      (node (ref "R40") (pin "2") (pinfunction "2_2") (pintype "passive"))
    )
    (net (code "82") (name "Net-(DS21-A)") (class "Default")
      (node (ref "DS21") (pin "1") (pinfunction "A_1") (pintype "passive"))
      (node (ref "R41") (pin "2") (pinfunction "2_2") (pintype "passive"))
    )
    (net (code "83") (name "Net-(DS22-A)") (class "Default")
      (node (ref "DS22") (pin "1") (pinfunction "A_1") (pintype "passive"))
      (node (ref "R42") (pin "2") (pinfunction "2_2") (pintype "passive"))
    )
    (net (code "84") (name "VDC_3V3") (class "Default")
      (node (ref "D10") (pin "2") (pinfunction "K_2") (pintype "passive"))
      (node (ref "D11") (pin "2") (pinfunction "K_2") (pintype "passive"))
      (node (ref "D12") (pin "2") (pinfunction "K_2") (pintype "passive"))
      (node (ref "D13") (pin "2") (pinfunction "K_2") (pintype "passive"))
      (node (ref "D3") (pin "2") (pinfunction "K_2") (pintype "passive"))
      (node (ref "D4") (pin "2") (pinfunction "K_2") (pintype "passive"))
      (node (ref "D5") (pin "2") (pinfunction "K_2") (pintype "passive"))
      (node (ref "D6") (pin "2") (pinfunction "K_2") (pintype "passive"))
      (node (ref "D7") (pin "2") (pinfunction "K_2") (pintype "passive"))
      (node (ref "D8") (pin "2") (pinfunction "K_2") (pintype "passive"))
      (node (ref "D9") (pin "2") (pinfunction "K_2") (pintype "passive"))
      (node (ref "R10") (pin "1") (pinfunction "1_1") (pintype "passive"))
      (node (ref "R13") (pin "1") (pinfunction "1_1") (pintype "passive"))
      (node (ref "R14") (pin "1") (pinfunction "1_1") (pintype "passive"))
      (node (ref "R15") (pin "1") (pinfunction "1_1") (pintype "passive"))
      (node (ref "R18") (pin "1") (pinfunction "1_1") (pintype "passive"))
      (node (ref "R19") (pin "1") (pinfunction "1_1") (pintype "passive"))
      (node (ref "R22") (pin "1") (pinfunction "1_1") (pintype "passive"))
      (node (ref "R23") (pin "1") (pinfunction "1_1") (pintype "passive"))
      (node (ref "R24") (pin "1") (pinfunction "1_1") (pintype "passive"))
      (node (ref "R27") (pin "1") (pinfunction "1_1") (pintype "passive"))
      (node (ref "R28") (pin "1") (pinfunction "1_1") (pintype "passive"))
      (node (ref "R31") (pin "1") (pinfunction "1_1") (pintype "passive"))
      (node (ref "R32") (pin "1") (pinfunction "1_1") (pintype "passive"))
      (node (ref "R34") (pin "1") (pinfunction "1_1") (pintype "passive"))
      (node (ref "R35") (pin "1") (pinfunction "1_1") (pintype "passive"))
      (node (ref "R36") (pin "1") (pinfunction "1_1") (pintype "passive"))
      (node (ref "R37") (pin "1") (pinfunction "1_1") (pintype "passive"))
      (node (ref "R38") (pin "1") (pinfunction "1_1") (pintype "passive"))
      (node (ref "R39") (pin "1") (pinfunction "1_1") (pintype "passive"))
      (node (ref "R40") (pin "1") (pinfunction "1_1") (pintype "passive"))
      (node (ref "R41") (pin "1") (pinfunction "1_1") (pintype "passive"))
      (node (ref "R42") (pin "1") (pinfunction "1_1") (pintype "passive"))
      (node (ref "R45") (pin "1") (pinfunction "1_1") (pintype "passive"))
      (node (ref "R46") (pin "1") (pinfunction "1_1") (pintype "passive"))
      (node (ref "R47") (pin "1") (pinfunction "1_1") (pintype "passive"))
      (node (ref "R48") (pin "1") (pinfunction "1_1") (pintype "passive"))
      (node (ref "R49") (pin "1") (pinfunction "1_1") (pintype "passive"))
      (node (ref "R50") (pin "1") (pinfunction "1_1") (pintype "passive"))
      (node (ref "R51") (pin "1") (pinfunction "1_1") (pintype "passive"))
      (node (ref "R52") (pin "1") (pinfunction "1_1") (pintype "passive"))
      (node (ref "R53") (pin "1") (pinfunction "1_1") (pintype "passive"))
      (node (ref "R54") (pin "1") (pinfunction "1_1") (pintype "passive"))
      (node (ref "R55") (pin "1") (pinfunction "1_1") (pintype "passive"))
      (node (ref "R56") (pin "1") (pinfunction "1_1") (pintype "passive"))
      (node (ref "R57") (pin "1") (pinfunction "1_1") (pintype "passive"))
      (node (ref "R58") (pin "1") (pinfunction "1_1") (pintype "passive"))
      (node (ref "R59") (pin "1") (pinfunction "1_1") (pintype "passive"))
      (node (ref "R60") (pin "1") (pinfunction "1_1") (pintype "passive"))
    )
  )
)
